# ai_breakout_ft2323RL.net
KiCad netlist of a schematic drawn in EAGLE
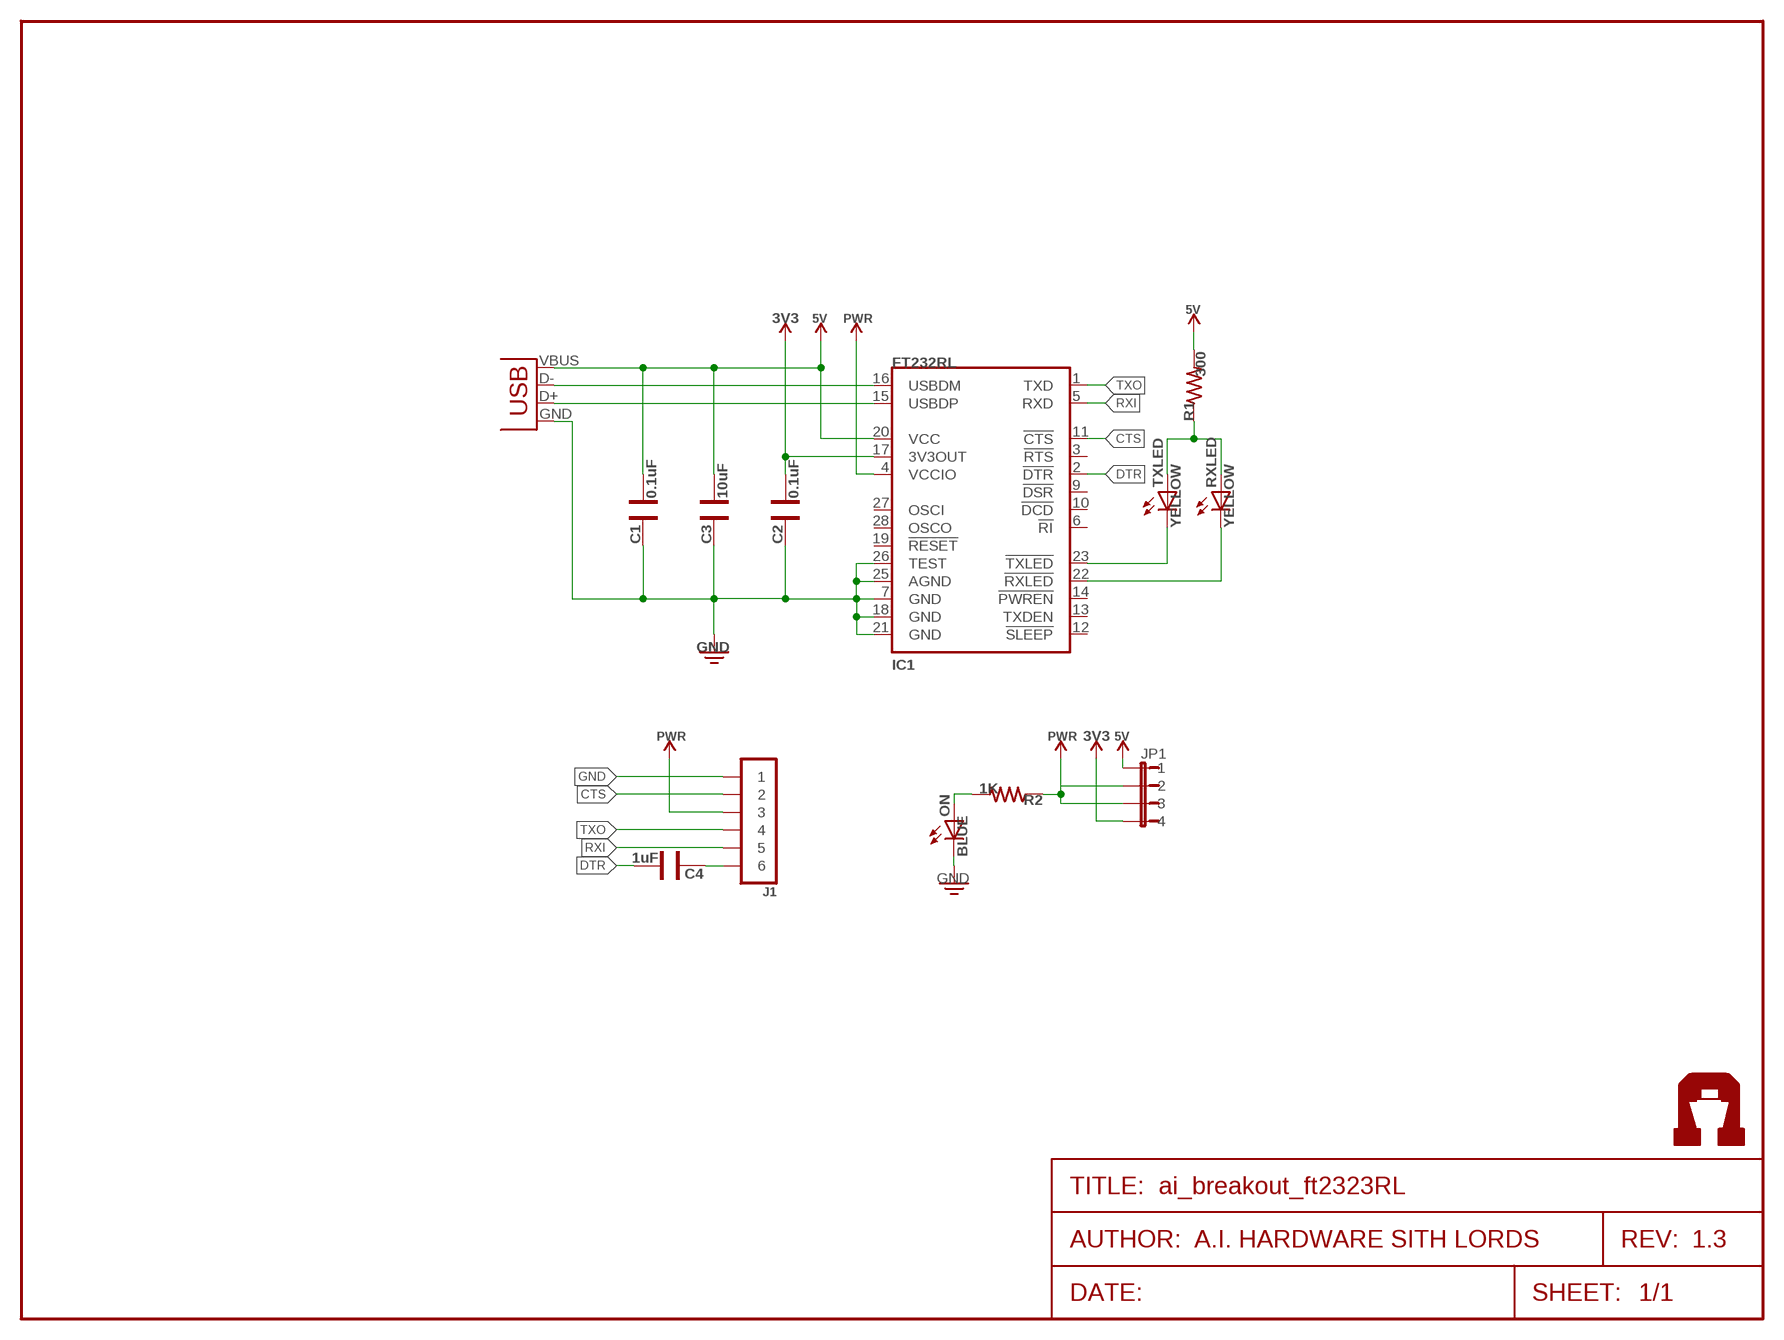
[diagram p0: schematic, sheet 1]

(export (version "E")
  (design (tool "Eeschema 10.0.6"))
  (components
    (comp (ref "C1")
      (value "0.1uF")
      (footprint "eagle-import:CAP-0603")
      (libsource (lib "eagle-import") (part "CAP0603"))
    )
    (comp (ref "C2")
      (value "0.1uF")
      (footprint "eagle-import:CAP-0603")
      (libsource (lib "eagle-import") (part "CAP0603"))
    )
    (comp (ref "C3")
      (value "10uF")
      (footprint "eagle-import:CAP-0603")
      (libsource (lib "eagle-import") (part "CAP0603"))
    )
    (comp (ref "C4")
      (value "1uF")
      (footprint "eagle-import:CAP-0603")
      (libsource (lib "eagle-import") (part "CAP0603"))
    )
    (comp (ref "IC1")
      (value "FT2332RL")
      (footprint "eagle-import:SSOP28-LD")
      (libsource (lib "eagle-import") (part "FT2332RL"))
    )
    (comp (ref "J1")
      (value "1X06LONG")
      (footprint "eagle-import:1X06-LONG")
      (libsource (lib "eagle-import") (part "1X06LONG"))
    )
    (comp (ref "JP1")
      (value "1X04-PJ")
      (footprint "eagle-import:1X04")
      (libsource (lib "eagle-import") (part "1X04-PJ"))
    )
    (comp (ref "ON")
      (value "BLUE")
      (footprint "eagle-import:LED-0603")
      (libsource (lib "eagle-import") (part "LED0603"))
    )
    (comp (ref "R1")
      (value "300")
      (footprint "eagle-import:RES-0603")
      (libsource (lib "eagle-import") (part "RES0603"))
    )
    (comp (ref "R2")
      (value "1K")
      (footprint "eagle-import:RES-0603")
      (libsource (lib "eagle-import") (part "RES0603"))
    )
    (comp (ref "RXLED")
      (value "YELLOW")
      (footprint "eagle-import:LED-0603")
      (libsource (lib "eagle-import") (part "LED0603"))
    )
    (comp (ref "TXLED")
      (value "YELLOW")
      (footprint "eagle-import:LED-0603")
      (libsource (lib "eagle-import") (part "LED0603"))
    )
    (comp (ref "U$3")
      (value "AI-LOGOL")
      (footprint "eagle-import:AI-LOGO-L")
      (libsource (lib "eagle-import") (part "AI-LOGOL"))
    )
    (comp (ref "USB1")
      (value "USBMICROB-TH")
      (footprint "eagle-import:USB-MICROB-TH")
      (libsource (lib "eagle-import") (part "USBMICROB-TH"))
    )
  )
  (nets
    (net (code "1") (name "3V3") (class "Default")
      (node (ref "C2") (pin "1") (pinfunction "1_1") (pintype "passive"))
      (node (ref "IC1") (pin "17") (pinfunction "3V3OUT_17") (pintype "power_in"))
      (node (ref "JP1") (pin "4") (pinfunction "4_4") (pintype "passive"))
    )
    (net (code "2") (name "5V") (class "Default")
      (node (ref "C1") (pin "1") (pinfunction "1_1") (pintype "passive"))
      (node (ref "C3") (pin "1") (pinfunction "1_1") (pintype "passive"))
      (node (ref "IC1") (pin "20") (pinfunction "VCC_20") (pintype "power_in"))
      (node (ref "JP1") (pin "1") (pinfunction "1_1") (pintype "passive"))
      (node (ref "R1") (pin "2") (pinfunction "2_2") (pintype "passive"))
      (node (ref "USB1") (pin "VBUS") (pinfunction "VBUS_VBUS") (pintype "bidirectional"))
    )
    (net (code "3") (name "CTS") (class "Default")
      (node (ref "IC1") (pin "11") (pinfunction "~{CTS}_11") (pintype "input"))
      (node (ref "J1") (pin "2") (pinfunction "2_2") (pintype "bidirectional"))
    )
    (net (code "4") (name "DTR") (class "Default")
      (node (ref "C4") (pin "1") (pinfunction "1_1") (pintype "passive"))
      (node (ref "IC1") (pin "2") (pinfunction "~{DTR}_2") (pintype "output"))
    )
    (net (code "5") (name "GND") (class "Default")
      (node (ref "C1") (pin "2") (pinfunction "2_2") (pintype "passive"))
      (node (ref "C2") (pin "2") (pinfunction "2_2") (pintype "passive"))
      (node (ref "C3") (pin "2") (pinfunction "2_2") (pintype "passive"))
      (node (ref "IC1") (pin "18") (pinfunction "GND_18") (pintype "power_in"))
      (node (ref "IC1") (pin "21") (pinfunction "GND_21") (pintype "power_in"))
      (node (ref "IC1") (pin "25") (pinfunction "AGND_25") (pintype "power_in"))
      (node (ref "IC1") (pin "26") (pinfunction "TEST_26") (pintype "input"))
      (node (ref "IC1") (pin "7") (pinfunction "GND_7") (pintype "power_in"))
      (node (ref "J1") (pin "1") (pinfunction "1_1") (pintype "bidirectional"))
      (node (ref "ON") (pin "C") (pinfunction "C_C") (pintype "passive"))
      (node (ref "USB1") (pin "GND") (pinfunction "GND_GND") (pintype "bidirectional"))
    )
    (net (code "6") (name "Net-(C4-Pad2)") (class "Default")
      (node (ref "C4") (pin "2") (pinfunction "2_2") (pintype "passive"))
      (node (ref "J1") (pin "6") (pinfunction "6_6") (pintype "bidirectional"))
    )
    (net (code "7") (name "Net-(IC1-USBDM)") (class "Default")
      (node (ref "IC1") (pin "16") (pinfunction "USBDM_16") (pintype "bidirectional"))
      (node (ref "USB1") (pin "D-") (pinfunction "D-_D-") (pintype "bidirectional"))
    )
    (net (code "8") (name "Net-(IC1-USBDP)") (class "Default")
      (node (ref "IC1") (pin "15") (pinfunction "USBDP_15") (pintype "bidirectional"))
      (node (ref "USB1") (pin "D+") (pinfunction "D+_D+") (pintype "bidirectional"))
    )
    (net (code "9") (name "Net-(IC1-~{RXLED})") (class "Default")
      (node (ref "IC1") (pin "22") (pinfunction "~{RXLED}_22") (pintype "input"))
      (node (ref "RXLED") (pin "C") (pinfunction "C_C") (pintype "passive"))
    )
    (net (code "10") (name "Net-(IC1-~{TXLED})") (class "Default")
      (node (ref "IC1") (pin "23") (pinfunction "~{TXLED}_23") (pintype "input"))
      (node (ref "TXLED") (pin "C") (pinfunction "C_C") (pintype "passive"))
    )
    (net (code "11") (name "Net-(ON-PadA)") (class "Default")
      (node (ref "ON") (pin "A") (pinfunction "A_A") (pintype "passive"))
      (node (ref "R2") (pin "2") (pinfunction "2_2") (pintype "passive"))
    )
    (net (code "12") (name "Net-(R1-Pad1)") (class "Default")
      (node (ref "R1") (pin "1") (pinfunction "1_1") (pintype "passive"))
      (node (ref "RXLED") (pin "A") (pinfunction "A_A") (pintype "passive"))
      (node (ref "TXLED") (pin "A") (pinfunction "A_A") (pintype "passive"))
    )
    (net (code "13") (name "PWR") (class "Default")
      (node (ref "IC1") (pin "4") (pinfunction "VCCIO_4") (pintype "power_in"))
      (node (ref "J1") (pin "3") (pinfunction "3_3") (pintype "bidirectional"))
      (node (ref "JP1") (pin "2") (pinfunction "2_2") (pintype "passive"))
      (node (ref "JP1") (pin "3") (pinfunction "3_3") (pintype "passive"))
      (node (ref "R2") (pin "1") (pinfunction "1_1") (pintype "passive"))
    )
    (net (code "14") (name "RXI") (class "Default")
      (node (ref "IC1") (pin "5") (pinfunction "RXD_5") (pintype "input"))
      (node (ref "J1") (pin "5") (pinfunction "5_5") (pintype "bidirectional"))
    )
    (net (code "15") (name "TXO") (class "Default")
      (node (ref "IC1") (pin "1") (pinfunction "TXD_1") (pintype "output"))
      (node (ref "J1") (pin "4") (pinfunction "4_4") (pintype "bidirectional"))
    )
    (net (code "16") (name "unconnected-(IC1-OSCI-Pad27)") (class "Default")
      (node (ref "IC1") (pin "27") (pinfunction "OSCI_27") (pintype "no_connect"))
    )
    (net (code "17") (name "unconnected-(IC1-OSCO-Pad28)") (class "Default")
      (node (ref "IC1") (pin "28") (pinfunction "OSCO_28") (pintype "output"))
    )
    (net (code "18") (name "unconnected-(IC1-TXDEN-Pad13)") (class "Default")
      (node (ref "IC1") (pin "13") (pinfunction "TXDEN_13") (pintype "no_connect"))
    )
    (net (code "19") (name "unconnected-(IC1-~{DCD}-Pad10)") (class "Default")
      (node (ref "IC1") (pin "10") (pinfunction "~{DCD}_10") (pintype "no_connect"))
    )
    (net (code "20") (name "unconnected-(IC1-~{DSR}-Pad9)") (class "Default")
      (node (ref "IC1") (pin "9") (pinfunction "~{DSR}_9") (pintype "no_connect"))
    )
    (net (code "21") (name "unconnected-(IC1-~{PWREN}-Pad14)") (class "Default")
      (node (ref "IC1") (pin "14") (pinfunction "~{PWREN}_14") (pintype "no_connect"))
    )
    (net (code "22") (name "unconnected-(IC1-~{RESET}-Pad19)") (class "Default")
      (node (ref "IC1") (pin "19") (pinfunction "~{RESET}_19") (pintype "no_connect"))
    )
    (net (code "23") (name "unconnected-(IC1-~{RI}-Pad6)") (class "Default")
      (node (ref "IC1") (pin "6") (pinfunction "~{RI}_6") (pintype "no_connect"))
    )
    (net (code "24") (name "unconnected-(IC1-~{RTS}-Pad3)") (class "Default")
      (node (ref "IC1") (pin "3") (pinfunction "~{RTS}_3") (pintype "output"))
    )
    (net (code "25") (name "unconnected-(IC1-~{SLEEP}-Pad12)") (class "Default")
      (node (ref "IC1") (pin "12") (pinfunction "~{SLEEP}_12") (pintype "no_connect"))
    )
  )
)
